# sensor_otomatis_ldr.net
KiCad netlist of a schematic drawn in EAGLE
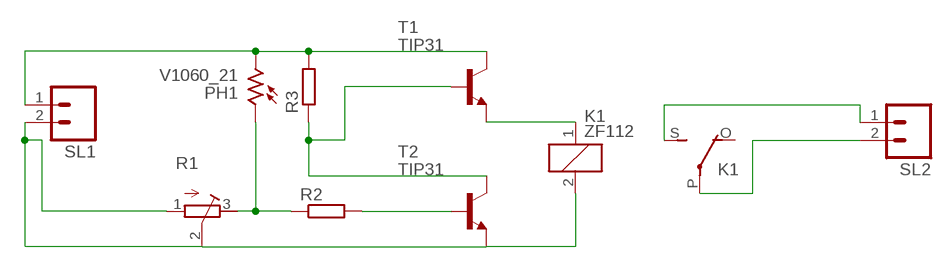
[diagram p0: schematic, sheet 1]

(export (version "E")
  (design (tool "Eeschema 10.0.6"))
  (components
    (comp (ref "K1")
      (value "ZF112")
      (footprint "eagle-import:ZF112")
      (libsource (lib "eagle-import") (part "ZF112"))
    )
    (comp (ref "PH1")
      (value "V1060_21")
      (footprint "eagle-import:TO-5_V10")
      (libsource (lib "eagle-import") (part "?1060V_21"))
    )
    (comp (ref "R1")
      (value "R-TRIMM3339P")
      (footprint "eagle-import:RTRIM3339P")
      (libsource (lib "eagle-import") (part "R-TRIMM3339P"))
    )
    (comp (ref "R2")
      (value "R-EU_0207/10")
      (footprint "eagle-import:0207_10")
      (libsource (lib "eagle-import") (part "R-EU_0207/10"))
    )
    (comp (ref "R3")
      (value "R-EU_0207/10")
      (footprint "eagle-import:0207_10")
      (libsource (lib "eagle-import") (part "R-EU_0207/10"))
    )
    (comp (ref "SL1")
      (value "M02")
      (footprint "eagle-import:02P")
      (libsource (lib "eagle-import") (part "M02"))
    )
    (comp (ref "SL2")
      (value "M02")
      (footprint "eagle-import:02P")
      (libsource (lib "eagle-import") (part "M02"))
    )
    (comp (ref "T1")
      (value "TIP31")
      (footprint "eagle-import:TO220")
      (libsource (lib "eagle-import") (part "TIP31"))
    )
    (comp (ref "T2")
      (value "TIP31")
      (footprint "eagle-import:TO220")
      (libsource (lib "eagle-import") (part "TIP31"))
    )
  )
  (nets
    (net (code "1") (name "Net-(K1-PadP)") (class "Default")
      (node (ref "K1") (pin "P") (pinfunction "P_P") (pintype "passive"))
      (node (ref "SL2") (pin "2") (pinfunction "2_2") (pintype "passive"))
    )
    (net (code "2") (name "Net-(K1-PadS)") (class "Default")
      (node (ref "K1") (pin "S") (pinfunction "S_S") (pintype "passive"))
      (node (ref "SL2") (pin "1") (pinfunction "1_1") (pintype "passive"))
    )
    (net (code "3") (name "Net-(R1-A)") (class "Default")
      (node (ref "K1") (pin "2") (pinfunction "2_2") (pintype "passive"))
      (node (ref "R1") (pin "1") (pinfunction "A_1") (pintype "passive"))
      (node (ref "R1") (pin "2") (pinfunction "S_2") (pintype "passive"))
      (node (ref "SL1") (pin "2") (pinfunction "2_2") (pintype "passive"))
      (node (ref "T2") (pin "3") (pinfunction "E_3") (pintype "passive"))
    )
    (net (code "4") (name "Net-(R1-E)") (class "Default")
      (node (ref "PH1") (pin "1") (pinfunction "1_1") (pintype "passive"))
      (node (ref "R1") (pin "3") (pinfunction "E_3") (pintype "passive"))
      (node (ref "R2") (pin "1") (pinfunction "1_1") (pintype "passive"))
    )
    (net (code "5") (name "Net-(T1-B)") (class "Default")
      (node (ref "R3") (pin "1") (pinfunction "1_1") (pintype "passive"))
      (node (ref "T1") (pin "1") (pinfunction "B_1") (pintype "passive"))
      (node (ref "T2") (pin "2") (pinfunction "C_2") (pintype "passive"))
    )
    (net (code "6") (name "Net-(T1-C)") (class "Default")
      (node (ref "PH1") (pin "2") (pinfunction "2_2") (pintype "passive"))
      (node (ref "R3") (pin "2") (pinfunction "2_2") (pintype "passive"))
      (node (ref "SL1") (pin "1") (pinfunction "1_1") (pintype "passive"))
      (node (ref "T1") (pin "2") (pinfunction "C_2") (pintype "passive"))
    )
    (net (code "7") (name "Net-(T1-E)") (class "Default")
      (node (ref "K1") (pin "1") (pinfunction "1_1") (pintype "passive"))
      (node (ref "T1") (pin "3") (pinfunction "E_3") (pintype "passive"))
    )
    (net (code "8") (name "Net-(T2-B)") (class "Default")
      (node (ref "R2") (pin "2") (pinfunction "2_2") (pintype "passive"))
      (node (ref "T2") (pin "1") (pinfunction "B_1") (pintype "passive"))
    )
    (net (code "9") (name "unconnected-(K1-PadO)") (class "Default")
      (node (ref "K1") (pin "O") (pinfunction "O_O") (pintype "passive"))
    )
  )
)
